# Barrido_de_temperatura.net
KiCad netlist of a schematic drawn in Altium Designer
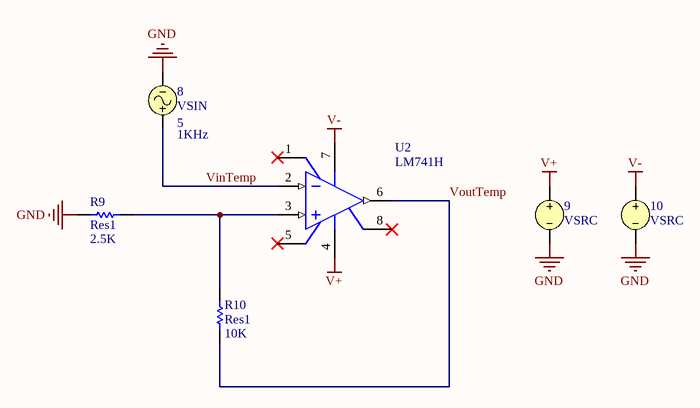
[diagram p0: Barrido de temperatura.SchDoc]

(export (version "E")
  (design (tool "Eeschema 10.0.6"))
  (components
    (comp (ref "8")
      (value "VSIN")
      (description "Sinusoidal Voltage Source")
      (fields
        (field (name "AMPLITUDE") "5")
        (field (name "FREQUENCY") "1KHz")
        (field (name "PUBLISHER") "Altium Limited")
      )
      (libsource (lib "Simulation Sources") (part "VSIN"))
    )
    (comp (ref "9")
      (value "VSRC")
      (description "Voltage Source")
      (fields (field (name "PUBLISHER") "Altium Limited"))
      (libsource (lib "Simulation Sources") (part "VSRC"))
    )
    (comp (ref "10")
      (value "VSRC")
      (description "Voltage Source")
      (fields (field (name "PUBLISHER") "Altium Limited"))
      (libsource (lib "Simulation Sources") (part "VSRC"))
    )
    (comp (ref "R9")
      (value "Res1")
      (footprint "AXIAL-0.3")
      (description "Resistor")
      (fields (field (name "ALTIUM_VALUE") "2.5K") (field (name "PUBLISHER") "Altium Limited"))
      (libsource (lib "Miscellaneous Devices") (part "Res1"))
    )
    (comp (ref "R10")
      (value "Res1")
      (footprint "AXIAL-0.3")
      (description "Resistor")
      (fields (field (name "ALTIUM_VALUE") "10K") (field (name "PUBLISHER") "Altium Limited"))
      (libsource (lib "Miscellaneous Devices") (part "Res1"))
    )
    (comp (ref "U2")
      (value "LM741H")
      (footprint "H08C")
      (description "Operational Amplifier, 8-pin TO-99")
      (fields
        (field (name "MANUFACTURER") "National Semiconductor")
        (field (name "PUBLISHER") "Altium Limited")
      )
      (libsource (lib "NSC Amplifier") (part "LM741H"))
    )
  )
  (nets
    (net (code "1") (name "/VinTemp") (class "Default")
      (node (ref "8") (pin "1") (pinfunction "1_1") (pintype "passive"))
      (node (ref "U2") (pin "2") (pinfunction "IN-_2") (pintype "input"))
    )
    (net (code "2") (name "/VoutTemp") (class "Default")
      (node (ref "R10") (pin "2") (pinfunction "2_2") (pintype "passive"))
      (node (ref "U2") (pin "6") (pinfunction "OUT_6") (pintype "output"))
    )
    (net (code "3") (name "GND") (class "Default")
      (node (ref "10") (pin "2") (pinfunction "2_2") (pintype "passive"))
      (node (ref "8") (pin "2") (pinfunction "2_2") (pintype "passive"))
      (node (ref "9") (pin "2") (pinfunction "2_2") (pintype "passive"))
      (node (ref "R9") (pin "1") (pinfunction "1_1") (pintype "passive"))
    )
    (net (code "4") (name "Net-(U2-IN+)") (class "Default")
      (node (ref "R10") (pin "1") (pinfunction "1_1") (pintype "passive"))
      (node (ref "R9") (pin "2") (pinfunction "2_2") (pintype "passive"))
      (node (ref "U2") (pin "3") (pinfunction "IN+_3") (pintype "input"))
    )
    (net (code "5") (name "V+") (class "Default")
      (node (ref "9") (pin "1") (pinfunction "1_1") (pintype "passive"))
      (node (ref "U2") (pin "4") (pinfunction "V-_4") (pintype "power_in"))
    )
    (net (code "6") (name "V-") (class "Default")
      (node (ref "10") (pin "1") (pinfunction "1_1") (pintype "passive"))
      (node (ref "U2") (pin "7") (pinfunction "V+_7") (pintype "power_in"))
    )
    (net (code "7") (name "unconnected-(U2-NC-Pad8)") (class "Default")
      (node (ref "U2") (pin "8") (pinfunction "NC_8") (pintype "passive+no_connect"))
    )
    (net (code "8") (name "unconnected-(U2-OFS_NULL-Pad1)") (class "Default")
      (node (ref "U2") (pin "1") (pinfunction "OFS_NULL_1") (pintype "passive+no_connect"))
    )
    (net (code "9") (name "unconnected-(U2-OFS_NULL-Pad5)") (class "Default")
      (node (ref "U2") (pin "5") (pinfunction "OFS_NULL_5") (pintype "passive+no_connect"))
    )
  )
)
